# Power2.net
KiCad netlist of a schematic drawn in Altium Designer
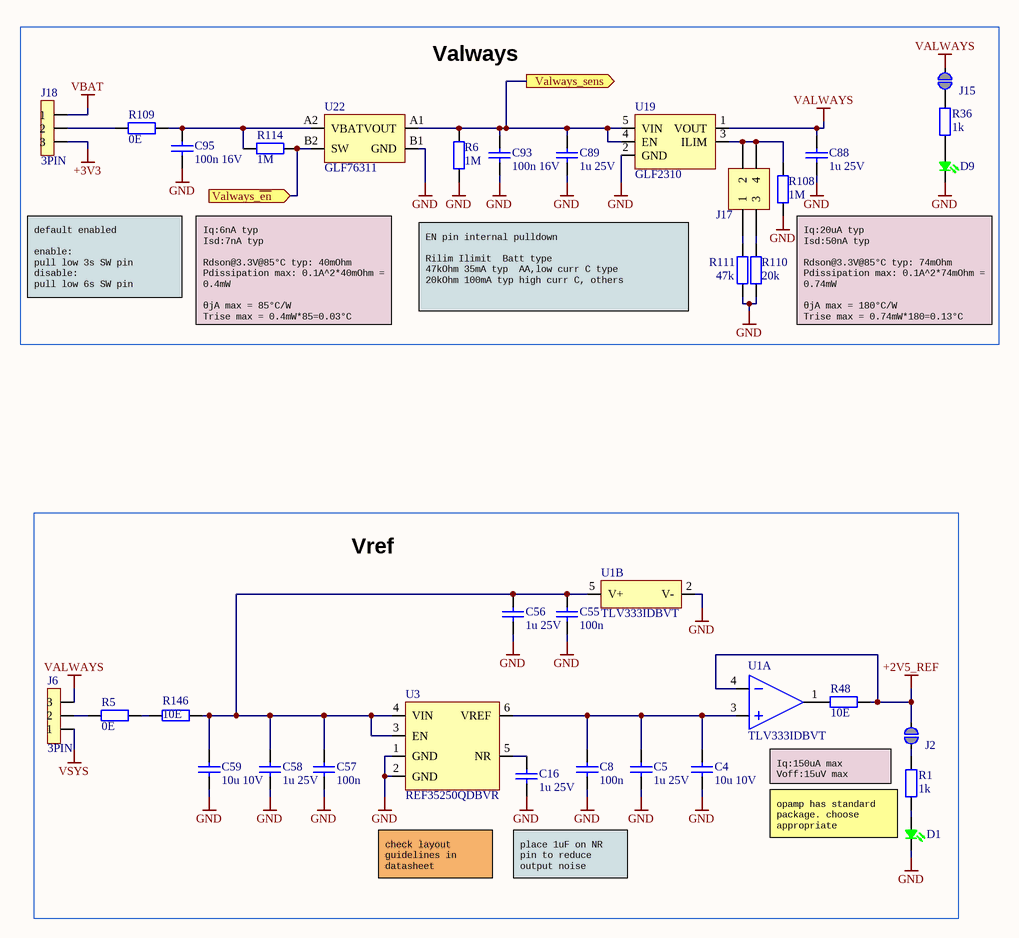
[diagram p0: Power2.SchDoc]

(export (version "E")
  (design (tool "Eeschema 10.0.6"))
  (components
    (comp (ref "C4")
      (value "10u 10V")
      (footprint "CAPC1608X09N")
      (description "10uF 10V ±20% X7T")
      (libsource (lib "DCI") (part "Capacitor_NP"))
    )
    (comp (ref "C5")
      (value "1u 25V")
      (footprint "CAPC1608X09N")
      (description "1UF, 25V, 10%, 0603, X7R")
      (libsource (lib "DCI") (part "Capacitor_NP"))
    )
    (comp (ref "C8")
      (value "100n")
      (footprint "CAPC1608X09N")
      (description "100nF 50V 10% X7R")
      (libsource (lib "DCI") (part "Capacitor_NP"))
    )
    (comp (ref "C16")
      (value "1u 25V")
      (footprint "CAPC1608X09N")
      (description "1UF, 25V, 10%, 0603, X7R")
      (libsource (lib "DCI") (part "Capacitor_NP"))
    )
    (comp (ref "C55")
      (value "100n")
      (footprint "CAPC1608X09N")
      (description "100nF 50V 10% X7R")
      (libsource (lib "DCI") (part "Capacitor_NP"))
    )
    (comp (ref "C56")
      (value "1u 25V")
      (footprint "CAPC1608X09N")
      (description "1UF, 25V, 10%, 0603, X7R")
      (libsource (lib "DCI") (part "Capacitor_NP"))
    )
    (comp (ref "C57")
      (value "100n")
      (footprint "CAPC1608X09N")
      (description "100nF 50V 10% X7R")
      (libsource (lib "DCI") (part "Capacitor_NP"))
    )
    (comp (ref "C58")
      (value "1u 25V")
      (footprint "CAPC1608X09N")
      (description "1UF, 25V, 10%, 0603, X7R")
      (libsource (lib "DCI") (part "Capacitor_NP"))
    )
    (comp (ref "C59")
      (value "10u 10V")
      (footprint "CAPC1608X09N")
      (description "10uF 10V ±20% X7T")
      (libsource (lib "DCI") (part "Capacitor_NP"))
    )
    (comp (ref "C88")
      (value "1u 25V")
      (footprint "CAPC1608X09N")
      (description "1UF, 25V, 10%, 0603, X7R")
      (libsource (lib "DCI") (part "Capacitor_NP"))
    )
    (comp (ref "C89")
      (value "1u 25V")
      (footprint "CAPC1608X09N")
      (description "1UF, 25V, 10%, 0603, X7R")
      (libsource (lib "DCI") (part "Capacitor_NP"))
    )
    (comp (ref "C93")
      (value "100n 16V")
      (footprint "CAPC1005X05N")
      (description "100nF, 16V, 10%, X7R")
      (libsource (lib "DCI") (part "Capacitor_NP"))
    )
    (comp (ref "C95")
      (value "100n 16V")
      (footprint "CAPC1005X05N")
      (description "100nF, 16V, 10%, X7R")
      (libsource (lib "DCI") (part "Capacitor_NP"))
    )
    (comp (ref "D1")
      (value "~")
      (footprint "LED_0603_ANODE")
      (description "Led Groen 0603")
      (libsource (lib "DCI") (part "LED_GREEN"))
    )
    (comp (ref "D9")
      (value "~")
      (footprint "LED_0603_ANODE")
      (description "Led Groen 0603")
      (libsource (lib "DCI") (part "LED_GREEN"))
    )
    (comp (ref "J2")
      (value "Solderbridge - Normally Open")
      (footprint "Solderbridge NO")
      (description "Solderbridge  - Normally Open")
      (libsource (lib "PCBComponenten") (part "SolderbridgeNO"))
    )
    (comp (ref "J6")
      (value "3PIN")
      (footprint "CON-003G001-003")
      (description "pinh 1x3/straight/Au/1.27pitch")
      (libsource (lib "DCI") (part "3PIN"))
    )
    (comp (ref "J15")
      (value "Solderbridge - Normally Open")
      (footprint "Solderbridge NO")
      (description "Solderbridge  - Normally Open")
      (libsource (lib "PCBComponenten") (part "SolderbridgeNO"))
    )
    (comp (ref "J17")
      (value "2X2PIN")
      (footprint "CON-003G000-004")
      (description "pinh 2x2/straight/Au/1.27pitch")
      (libsource (lib "DCI") (part "2X2PIN"))
    )
    (comp (ref "J18")
      (value "3PIN")
      (footprint "CON-003G001-003")
      (description "pinh 1x3/straight/Au/1.27pitch")
      (libsource (lib "") (part "3PIN_1"))
    )
    (comp (ref "R1")
      (value "1k")
      (footprint "RESC1608X13N")
      (description "1K, 100mW, 1%")
      (libsource (lib "") (part "Resistor_3"))
    )
    (comp (ref "R5")
      (value "0E")
      (footprint "RESC1005X04N")
      (description "0E, 62.5mW, 1%")
      (libsource (lib "") (part "Resistor_2"))
    )
    (comp (ref "R6")
      (value "1M")
      (footprint "RESC1005x04N")
      (description "1M, 62.5mW, 1%")
      (libsource (lib "DCI") (part "Resistor"))
    )
    (comp (ref "R36")
      (value "1k")
      (footprint "RESC1608X13N")
      (description "1K, 100mW, 1%")
      (libsource (lib "") (part "Resistor_3"))
    )
    (comp (ref "R48")
      (value "10E")
      (footprint "RESC1608X13N")
      (description "10E 0.1W 1%")
      (libsource (lib "") (part "Resistor_2"))
    )
    (comp (ref "R108")
      (value "1M")
      (footprint "RESC1005x04N")
      (description "1M, 62.5mW, 1%")
      (libsource (lib "") (part "Resistor_1"))
    )
    (comp (ref "R109")
      (value "0E")
      (footprint "RESC1005X04N")
      (description "0E, 62.5mW, 1%")
      (libsource (lib "") (part "Resistor_2"))
    )
    (comp (ref "R110")
      (value "20k")
      (footprint "RESC1608X13N")
      (description "20k 100mW, 1%")
      (libsource (lib "") (part "Resistor_1"))
    )
    (comp (ref "R111")
      (value "47k")
      (footprint "RESC1608X13N")
      (description "47k 100mW 1%")
      (libsource (lib "") (part "Resistor_1"))
    )
    (comp (ref "R114")
      (value "1M")
      (footprint "RESC1005x04N")
      (description "1M, 62.5mW, 1%")
      (libsource (lib "") (part "Resistor_4"))
    )
    (comp (ref "R146")
      (value "10E")
      (footprint "RESC1608X13N")
      (description "10E 0.1W 1%")
      (libsource (lib "") (part "Resistor_2"))
    )
    (comp (ref "U1")
      (value "TLV333IDBVT")
      (footprint "SOT95P300X145-5N")
      (description "Op-Amp zero drift")
      (libsource (lib "") (part "AMP_1CH_1"))
    )
    (comp (ref "U3")
      (value "REF35250QDBVR")
      (footprint "SOT95P300X145-6N")
      (description "REF35250QDBVR, 2,5V")
      (libsource (lib "DCI") (part "REF_REF35xx_SOT23-6"))
    )
    (comp (ref "U19")
      (value "GLF2310")
      (footprint "SOT95P280X115-5N")
      (description "load sw adj current limit 5.5V")
      (libsource (lib "DCI") (part "SW_GLF2310A-T1"))
    )
    (comp (ref "U22")
      (value "GLF76311")
      (footprint "BGA4C50P2X2_97X97X55")
      (description "Smart load sw, 2A, 5.5V")
      (libsource (lib "DCI") (part "GLF76311"))
    )
  )
  (nets
    (net (code "1") (name "+2V5_REF") (class "Default")
      (node (ref "J2") (pin "2") (pinfunction "2_2") (pintype "passive"))
      (node (ref "R48") (pin "2") (pinfunction "2_2") (pintype "passive"))
      (node (ref "U1") (pin "4") (pinfunction "IN-_4") (pintype "passive"))
    )
    (net (code "2") (name "+3V3") (class "Default")
      (node (ref "J18") (pin "3") (pinfunction "3_3") (pintype "passive"))
    )
    (net (code "3") (name "/Valways_sens") (class "Default")
      (node (ref "C89") (pin "2") (pinfunction "2_2") (pintype "passive"))
      (node (ref "C93") (pin "2") (pinfunction "2_2") (pintype "passive"))
      (node (ref "R6") (pin "1") (pinfunction "1_1") (pintype "passive"))
      (node (ref "U19") (pin "4") (pinfunction "EN_4") (pintype "passive"))
      (node (ref "U19") (pin "5") (pinfunction "VIN_5") (pintype "passive"))
      (node (ref "U22") (pin "A1") (pinfunction "VOUT_A1") (pintype "passive"))
    )
    (net (code "4") (name "/Valways_~{en}") (class "Default")
      (node (ref "R114") (pin "1") (pinfunction "1_1") (pintype "passive"))
      (node (ref "U22") (pin "B2") (pinfunction "SW_B2") (pintype "passive"))
    )
    (net (code "5") (name "GND") (class "Default")
      (node (ref "C16") (pin "1") (pinfunction "1_1") (pintype "passive"))
      (node (ref "C4") (pin "1") (pinfunction "1_1") (pintype "passive"))
      (node (ref "C5") (pin "1") (pinfunction "1_1") (pintype "passive"))
      (node (ref "C55") (pin "1") (pinfunction "1_1") (pintype "passive"))
      (node (ref "C56") (pin "1") (pinfunction "1_1") (pintype "passive"))
      (node (ref "C57") (pin "1") (pinfunction "1_1") (pintype "passive"))
      (node (ref "C58") (pin "1") (pinfunction "1_1") (pintype "passive"))
      (node (ref "C59") (pin "1") (pinfunction "1_1") (pintype "passive"))
      (node (ref "C8") (pin "1") (pinfunction "1_1") (pintype "passive"))
      (node (ref "C88") (pin "1") (pinfunction "1_1") (pintype "passive"))
      (node (ref "C89") (pin "1") (pinfunction "1_1") (pintype "passive"))
      (node (ref "C93") (pin "1") (pinfunction "1_1") (pintype "passive"))
      (node (ref "C95") (pin "1") (pinfunction "1_1") (pintype "passive"))
      (node (ref "D1") (pin "C") (pinfunction "C_C") (pintype "passive"))
      (node (ref "D9") (pin "C") (pinfunction "C_C") (pintype "passive"))
      (node (ref "R108") (pin "1") (pinfunction "1_1") (pintype "passive"))
      (node (ref "R110") (pin "1") (pinfunction "1_1") (pintype "passive"))
      (node (ref "R111") (pin "1") (pinfunction "1_1") (pintype "passive"))
      (node (ref "R6") (pin "2") (pinfunction "2_2") (pintype "passive"))
      (node (ref "U1") (pin "2") (pinfunction "V-_2") (pintype "power_in"))
      (node (ref "U19") (pin "2") (pinfunction "GND_2") (pintype "passive"))
      (node (ref "U22") (pin "B1") (pinfunction "GND_B1") (pintype "passive"))
      (node (ref "U3") (pin "1") (pinfunction "GND_1") (pintype "passive"))
      (node (ref "U3") (pin "2") (pinfunction "GND_2") (pintype "passive"))
    )
    (net (code "6") (name "Net-(D1-PadA)") (class "Default")
      (node (ref "D1") (pin "A") (pinfunction "A_A") (pintype "passive"))
      (node (ref "R1") (pin "2") (pinfunction "2_2") (pintype "passive"))
    )
    (net (code "7") (name "Net-(D9-PadA)") (class "Default")
      (node (ref "D9") (pin "A") (pinfunction "A_A") (pintype "passive"))
      (node (ref "R36") (pin "2") (pinfunction "2_2") (pintype "passive"))
    )
    (net (code "8") (name "Net-(J2-Pad1)") (class "Default")
      (node (ref "J2") (pin "1") (pinfunction "1_1") (pintype "passive"))
      (node (ref "R1") (pin "1") (pinfunction "1_1") (pintype "passive"))
    )
    (net (code "9") (name "Net-(J6-Pad2)") (class "Default")
      (node (ref "J6") (pin "2") (pinfunction "2_2") (pintype "passive"))
      (node (ref "R5") (pin "1") (pinfunction "1_1") (pintype "passive"))
    )
    (net (code "10") (name "Net-(J15-Pad1)") (class "Default")
      (node (ref "J15") (pin "1") (pinfunction "1_1") (pintype "passive"))
      (node (ref "R36") (pin "1") (pinfunction "1_1") (pintype "passive"))
    )
    (net (code "11") (name "Net-(J17-Pad1)") (class "Default")
      (node (ref "J17") (pin "1") (pinfunction "1_1") (pintype "passive"))
      (node (ref "R111") (pin "2") (pinfunction "2_2") (pintype "passive"))
    )
    (net (code "12") (name "Net-(J17-Pad3)") (class "Default")
      (node (ref "J17") (pin "3") (pinfunction "3_3") (pintype "passive"))
      (node (ref "R110") (pin "2") (pinfunction "2_2") (pintype "passive"))
    )
    (net (code "13") (name "Net-(J18-Pad2)") (class "Default")
      (node (ref "J18") (pin "2") (pinfunction "2_2") (pintype "passive"))
      (node (ref "R109") (pin "1") (pinfunction "1_1") (pintype "passive"))
    )
    (net (code "14") (name "Net-(R146-Pad1)") (class "Default")
      (node (ref "R146") (pin "1") (pinfunction "1_1") (pintype "passive"))
      (node (ref "R5") (pin "2") (pinfunction "2_2") (pintype "passive"))
    )
    (net (code "15") (name "Net-(U1A-IN+)") (class "Default")
      (node (ref "C4") (pin "2") (pinfunction "2_2") (pintype "passive"))
      (node (ref "C5") (pin "2") (pinfunction "2_2") (pintype "passive"))
      (node (ref "C8") (pin "2") (pinfunction "2_2") (pintype "passive"))
      (node (ref "U1") (pin "3") (pinfunction "IN+_3") (pintype "passive"))
      (node (ref "U3") (pin "6") (pinfunction "VREF_6") (pintype "passive"))
    )
    (net (code "16") (name "Net-(U1A-OUT)") (class "Default")
      (node (ref "R48") (pin "1") (pinfunction "1_1") (pintype "passive"))
      (node (ref "U1") (pin "1") (pinfunction "OUT_1") (pintype "passive"))
    )
    (net (code "17") (name "Net-(U1B-V+)") (class "Default")
      (node (ref "C55") (pin "2") (pinfunction "2_2") (pintype "passive"))
      (node (ref "C56") (pin "2") (pinfunction "2_2") (pintype "passive"))
      (node (ref "C57") (pin "2") (pinfunction "2_2") (pintype "passive"))
      (node (ref "C58") (pin "2") (pinfunction "2_2") (pintype "passive"))
      (node (ref "C59") (pin "2") (pinfunction "2_2") (pintype "passive"))
      (node (ref "R146") (pin "2") (pinfunction "2_2") (pintype "passive"))
      (node (ref "U1") (pin "5") (pinfunction "V+_5") (pintype "power_in"))
      (node (ref "U3") (pin "3") (pinfunction "EN_3") (pintype "passive"))
      (node (ref "U3") (pin "4") (pinfunction "VIN_4") (pintype "passive"))
    )
    (net (code "18") (name "Net-(U3-NR)") (class "Default")
      (node (ref "C16") (pin "2") (pinfunction "2_2") (pintype "passive"))
      (node (ref "U3") (pin "5") (pinfunction "NR_5") (pintype "passive"))
    )
    (net (code "19") (name "Net-(U19-ILIM)") (class "Default")
      (node (ref "J17") (pin "2") (pinfunction "2_2") (pintype "passive"))
      (node (ref "J17") (pin "4") (pinfunction "4_4") (pintype "passive"))
      (node (ref "R108") (pin "2") (pinfunction "2_2") (pintype "passive"))
      (node (ref "U19") (pin "3") (pinfunction "ILIM_3") (pintype "passive"))
    )
    (net (code "20") (name "Net-(U22-VBAT)") (class "Default")
      (node (ref "C95") (pin "2") (pinfunction "2_2") (pintype "passive"))
      (node (ref "R109") (pin "2") (pinfunction "2_2") (pintype "passive"))
      (node (ref "R114") (pin "2") (pinfunction "2_2") (pintype "passive"))
      (node (ref "U22") (pin "A2") (pinfunction "VBAT_A2") (pintype "passive"))
    )
    (net (code "21") (name "VALWAYS") (class "Default")
      (node (ref "C88") (pin "2") (pinfunction "2_2") (pintype "passive"))
      (node (ref "J15") (pin "2") (pinfunction "2_2") (pintype "passive"))
      (node (ref "J6") (pin "3") (pinfunction "3_3") (pintype "passive"))
      (node (ref "U19") (pin "1") (pinfunction "VOUT_1") (pintype "passive"))
    )
    (net (code "22") (name "VBAT") (class "Default")
      (node (ref "J18") (pin "1") (pinfunction "1_1") (pintype "passive"))
    )
    (net (code "23") (name "VSYS") (class "Default")
      (node (ref "J6") (pin "1") (pinfunction "1_1") (pintype "passive"))
    )
  )
)
